# p7_power.net
KiCad netlist of a schematic drawn in Altium Designer
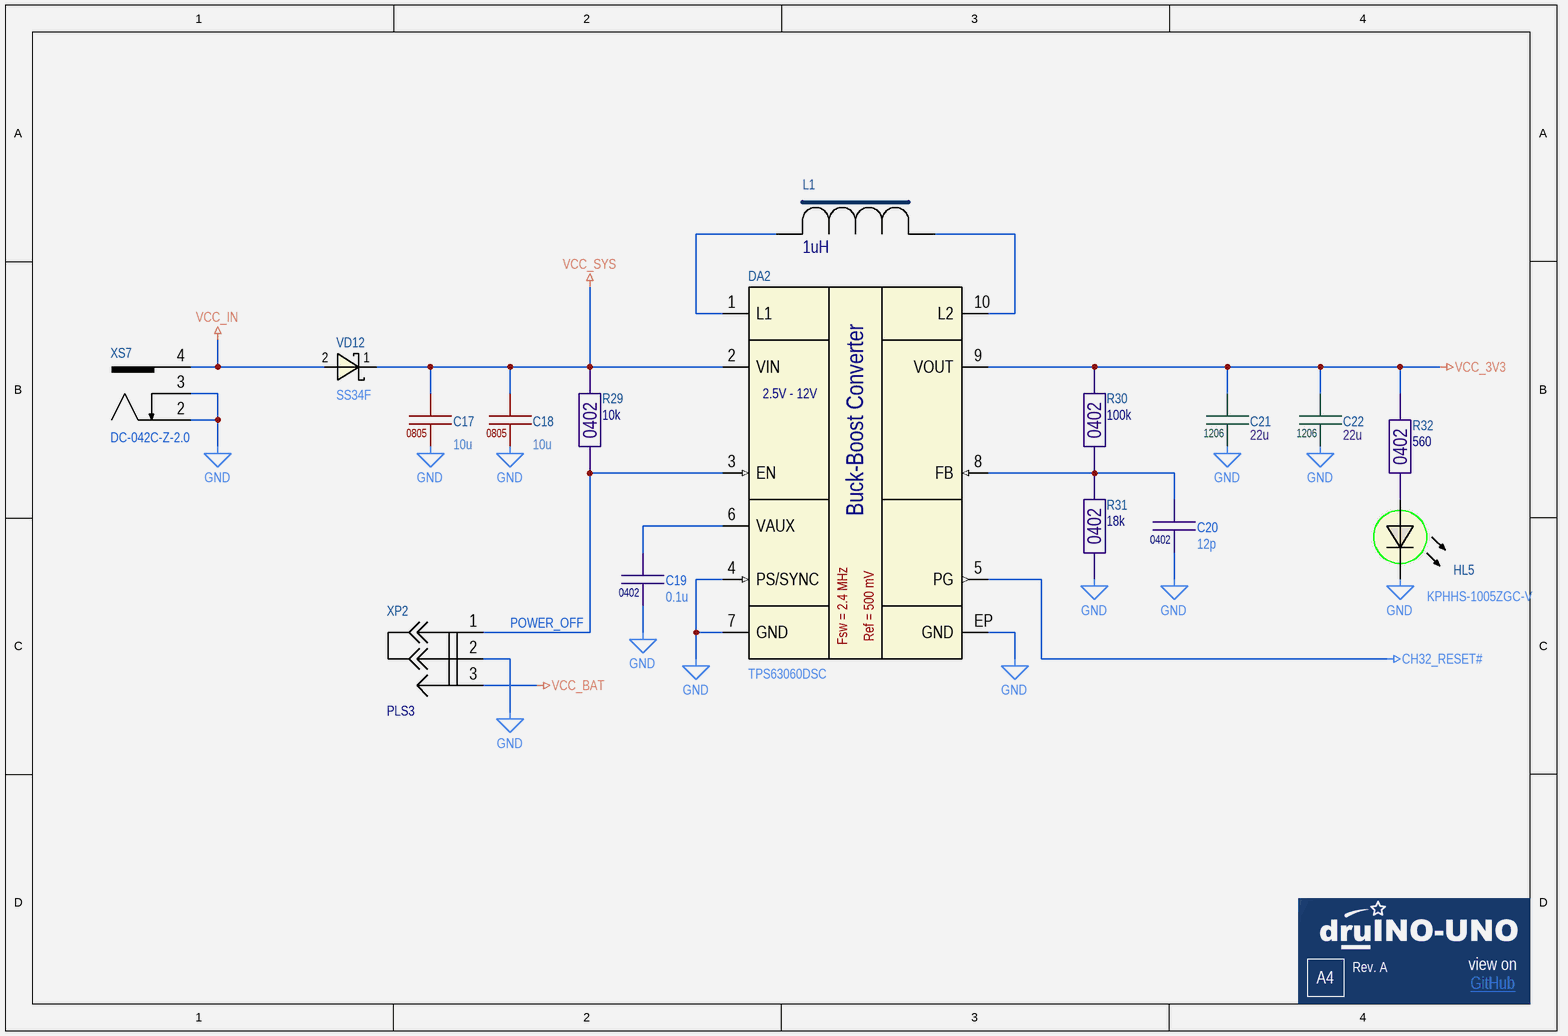
[diagram p0: p7_power.SchDoc]

(export (version "E")
  (design (tool "Eeschema 10.0.6"))
  (components
    (comp (ref "C17")
      (value "10u")
      (footprint "PcbLib_RC:CAP0805-0.75")
      (description "Capacitors 0805 package case")
      (fields
        (field (name "TOLERANCE") "± 10 %")
        (field (name "VOLTAGE") "25V")
        (field (name "PACKAGE") "0805")
      )
      (libsource (lib "Schlib_RC") (part "C0805"))
    )
    (comp (ref "C18")
      (value "10u")
      (footprint "PcbLib_RC:CAP0805-0.75")
      (description "Capacitors 0805 package case")
      (fields
        (field (name "TOLERANCE") "± 10 %")
        (field (name "VOLTAGE") "25V")
        (field (name "PACKAGE") "0805")
      )
      (libsource (lib "Schlib_RC") (part "C0805"))
    )
    (comp (ref "C19")
      (value "0.1u")
      (footprint "PcbLib_RC:CAP0402")
      (description "Capacitors 0402 package case")
      (fields
        (field (name "TOLERANCE") "± 5 %")
        (field (name "VOLTAGE") "50 V")
        (field (name "PACKAGE") "0402")
      )
      (libsource (lib "Schlib_RC") (part "C0402"))
    )
    (comp (ref "C20")
      (value "12p")
      (footprint "PcbLib_RC:CAP0402")
      (description "Capacitors 0402 package case")
      (fields
        (field (name "TOLERANCE") "± 1 %")
        (field (name "VOLTAGE") "50 V")
        (field (name "PACKAGE") "0402")
      )
      (libsource (lib "Schlib_RC") (part "C0402"))
    )
    (comp (ref "C21")
      (value "22u")
      (footprint "PcbLib_RC:CAP1206-1.8")
      (description "Capacitors 1206 package case")
      (fields
        (field (name "TOLERANCE") "± 20 %")
        (field (name "VOLTAGE") "16V")
        (field (name "PACKAGE") "1206")
      )
      (libsource (lib "Schlib_RC") (part "C1206"))
    )
    (comp (ref "C22")
      (value "22u")
      (footprint "PcbLib_RC:CAP1206-1.8")
      (description "Capacitors 1206 package case")
      (fields
        (field (name "TOLERANCE") "± 20 %")
        (field (name "VOLTAGE") "16V")
        (field (name "PACKAGE") "1206")
      )
      (libsource (lib "Schlib_RC") (part "C1206"))
    )
    (comp (ref "DA2")
      (value "TPS63060DSC")
      (footprint "PcbLib_ICs_part2:PWSON-10")
      (description "High Input Voltage, 2A Buck-Boost Converter")
      (fields (field (name "MANUFACTURER") "Texas Instruments"))
      (libsource (lib "Schlib_Texas_Instruments") (part "TPS63060DSC"))
    )
    (comp (ref "HL5")
      (value "KPHHS-1005ZGC-V")
      (footprint "PcbLib_Others:LED0402G525")
      (description "Green led (package case 0402)")
      (fields (field (name "MANUFACTURER") "Kingbright Company LLC."))
      (libsource (lib "Schlib_Kingbright") (part "KPHHS-1005ZGC-V"))
    )
    (comp (ref "L1")
      (value "IHLP2020BZERR22M01")
      (footprint "PcbLib_RC:IHLP1616")
      (description "Shielded SMD Power Inductors")
      (fields (field (name "MANUFACTURER") "Vishay Dale") (field (name "INDUCTANCE @ 100 KHZ") "1uH"))
      (libsource (lib "Schlib_Vishay") (part "IHLP1616BZER1R0M01"))
    )
    (comp (ref "R29")
      (value "10k")
      (footprint "PcbLib_RC:RES0402B")
      (description "Resistor 0402 package case")
      (fields
        (field (name "TOLERANCE") "± 1 %")
        (field (name "PART NUMBER") "RC0402FR-0710KL")
        (field (name "PACKAGE") "0402")
      )
      (libsource (lib "Schlib_RC") (part "R0402"))
    )
    (comp (ref "R30")
      (value "100k")
      (footprint "PcbLib_RC:RES0402B")
      (description "Resistor 0402 package case")
      (fields
        (field (name "TOLERANCE") "± 1 %")
        (field (name "PART NUMBER") "RC0402FR-07100KL")
        (field (name "PACKAGE") "0402")
      )
      (libsource (lib "Schlib_RC") (part "R0402"))
    )
    (comp (ref "R31")
      (value "18k")
      (footprint "PcbLib_RC:RES0402B")
      (description "Resistor 0402 package case")
      (fields
        (field (name "TOLERANCE") "± 1 %")
        (field (name "PART NUMBER") "RC0402FR-0718KL")
        (field (name "PACKAGE") "0402")
      )
      (libsource (lib "Schlib_RC") (part "R0402"))
    )
    (comp (ref "R32")
      (value "560")
      (footprint "PcbLib_RC:RES0402B")
      (description "Resistor 0402 package case")
      (fields
        (field (name "TOLERANCE") "± 1 %")
        (field (name "PART NUMBER") "RC0402FR-07560RL")
        (field (name "PACKAGE") "0402")
      )
      (libsource (lib "Schlib_RC") (part "R0402"))
    )
    (comp (ref "VD12")
      (value "SS34F")
      (footprint "PcbLib_Discrete:SMA-FL")
      (description "3A Schottky barrier rectifier")
      (fields (field (name "MANUFACTURER") "UMW"))
      (libsource (lib "Schlib_UMW") (part "SS34F"))
    )
    (comp (ref "XP2")
      (value "PLS3")
      (footprint "PcbLib_Pin_Headers:PLS-3")
      (libsource (lib "Schlib_OtherComponents") (part "PLS3"))
    )
    (comp (ref "XS7")
      (value "DC-042C-Z-2.0")
      (footprint "PcbLib_Others:DC-042C-Z-2.0")
      (description "Shrouded DC Power Receptacle 2mm 6.3mm 8A 24V")
      (fields (field (name "MANUFACTURER") "XKB Connectivity"))
      (libsource (lib "Schlib_OtherComponents") (part "DC-042C-Z-2.0"))
    )
  )
  (nets
    (net (code "1") (name "/POWER_OFF") (class "Default")
      (node (ref "DA2") (pin "3") (pinfunction "EN_3") (pintype "input"))
      (node (ref "R29") (pin "2") (pinfunction "2_2") (pintype "passive"))
      (node (ref "XP2") (pin "1") (pinfunction "1_1") (pintype "passive"))
    )
    (net (code "2") (name "CH32_RESET#") (class "Default")
      (node (ref "DA2") (pin "5") (pinfunction "PG_5") (pintype "output"))
    )
    (net (code "3") (name "GND") (class "Default")
      (node (ref "C17") (pin "1") (pinfunction "1_1") (pintype "passive"))
      (node (ref "C18") (pin "1") (pinfunction "1_1") (pintype "passive"))
      (node (ref "C19") (pin "2") (pinfunction "2_2") (pintype "passive"))
      (node (ref "C20") (pin "2") (pinfunction "2_2") (pintype "passive"))
      (node (ref "C21") (pin "1") (pinfunction "1_1") (pintype "passive"))
      (node (ref "C22") (pin "1") (pinfunction "1_1") (pintype "passive"))
      (node (ref "DA2") (pin "4") (pinfunction "PS/SYNC_4") (pintype "input"))
      (node (ref "DA2") (pin "7") (pinfunction "GND_7") (pintype "power_in"))
      (node (ref "DA2") (pin "EP") (pinfunction "GND_EP") (pintype "power_in"))
      (node (ref "HL5") (pin "1") (pinfunction "1_1") (pintype "passive"))
      (node (ref "R31") (pin "2") (pinfunction "2_2") (pintype "passive"))
      (node (ref "XP2") (pin "2") (pinfunction "2_2") (pintype "passive"))
      (node (ref "XS7") (pin "2") (pinfunction "2_2") (pintype "passive"))
      (node (ref "XS7") (pin "3") (pinfunction "3_3") (pintype "passive"))
    )
    (net (code "4") (name "Net-(DA2-FB)") (class "Default")
      (node (ref "C20") (pin "1") (pinfunction "1_1") (pintype "passive"))
      (node (ref "DA2") (pin "8") (pinfunction "FB_8") (pintype "input"))
      (node (ref "R30") (pin "2") (pinfunction "2_2") (pintype "passive"))
      (node (ref "R31") (pin "1") (pinfunction "1_1") (pintype "passive"))
    )
    (net (code "5") (name "Net-(DA2-L1)") (class "Default")
      (node (ref "DA2") (pin "1") (pinfunction "L1_1") (pintype "passive"))
      (node (ref "L1") (pin "1") (pinfunction "1_1") (pintype "passive"))
    )
    (net (code "6") (name "Net-(DA2-L2)") (class "Default")
      (node (ref "DA2") (pin "10") (pinfunction "L2_10") (pintype "passive"))
      (node (ref "L1") (pin "2") (pinfunction "2_2") (pintype "passive"))
    )
    (net (code "7") (name "Net-(DA2-VAUX)") (class "Default")
      (node (ref "C19") (pin "1") (pinfunction "1_1") (pintype "passive"))
      (node (ref "DA2") (pin "6") (pinfunction "VAUX_6") (pintype "passive"))
    )
    (net (code "8") (name "Net-(HL5-Pad2)") (class "Default")
      (node (ref "HL5") (pin "2") (pinfunction "2_2") (pintype "passive"))
      (node (ref "R32") (pin "1") (pinfunction "1_1") (pintype "passive"))
    )
    (net (code "9") (name "VCC_3V3") (class "Default")
      (node (ref "C21") (pin "2") (pinfunction "2_2") (pintype "passive"))
      (node (ref "C22") (pin "2") (pinfunction "2_2") (pintype "passive"))
      (node (ref "DA2") (pin "9") (pinfunction "VOUT_9") (pintype "power_in"))
      (node (ref "R30") (pin "1") (pinfunction "1_1") (pintype "passive"))
      (node (ref "R32") (pin "2") (pinfunction "2_2") (pintype "passive"))
    )
    (net (code "10") (name "VCC_BAT") (class "Default")
      (node (ref "XP2") (pin "3") (pinfunction "3_3") (pintype "passive"))
    )
    (net (code "11") (name "VCC_IN") (class "Default")
      (node (ref "VD12") (pin "2") (pinfunction "2_2") (pintype "passive"))
      (node (ref "XS7") (pin "4") (pinfunction "4_4") (pintype "passive"))
    )
    (net (code "12") (name "VCC_SYS") (class "Default")
      (node (ref "C17") (pin "2") (pinfunction "2_2") (pintype "passive"))
      (node (ref "C18") (pin "2") (pinfunction "2_2") (pintype "passive"))
      (node (ref "DA2") (pin "2") (pinfunction "VIN_2") (pintype "power_in"))
      (node (ref "R29") (pin "1") (pinfunction "1_1") (pintype "passive"))
      (node (ref "VD12") (pin "1") (pinfunction "1_1") (pintype "passive"))
    )
  )
)
